# Wireless.net
KiCad netlist of a schematic drawn in Altium Designer
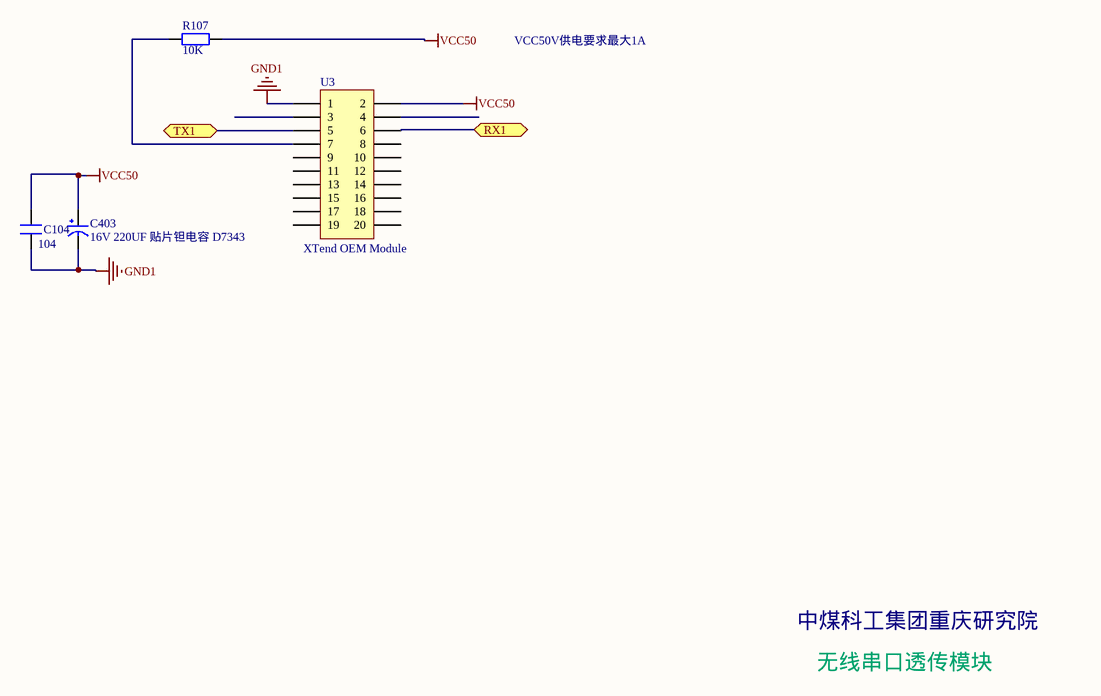
[diagram p0: Wireless.SchDoc]

(export (version "E")
  (design (tool "Eeschema 10.0.6"))
  (components
    (comp (ref "C104") (value "104") (footprint "1206") (libsource (lib "WarShip V3 STM32103封装库") (part "C")))
    (comp (ref "C403")
      (value "16V 220UF 贴片钽电容 D7343")
      (footprint "D型7343贴片钽电容")
      (libsource (lib "WarShip V3 STM32103封装库") (part "CAP"))
    )
    (comp (ref "R107")
      (value "10K")
      (footprint "1206")
      (description "Resistor")
      (fields (field (name "Comment") "Res2") (field (name "PUBLISHER") "Altium Limited"))
      (libsource (lib "Miscellaneous Devices") (part "Res2"))
    )
    (comp (ref "U3")
      (value "XTend OEM Module")
      (footprint "无线电台_PART_1")
      (description "Header, 10-Pin, Dual row")
      (fields (field (name "PUBLISHER") "Altium Limited"))
      (libsource (lib "Miscellaneous Connectors") (part "Header 10X2"))
    )
  )
  (nets
    (net (code "1") (name "/RX1") (class "Default")
      (node (ref "U3") (pin "6") (pinfunction "6_6") (pintype "passive"))
    )
    (net (code "2") (name "/TX1") (class "Default")
      (node (ref "U3") (pin "5") (pinfunction "5_5") (pintype "passive"))
    )
    (net (code "3") (name "GND1") (class "Default")
      (node (ref "C104") (pin "1") (pintype "passive"))
      (node (ref "C403") (pin "2") (pinfunction "GND_2") (pintype "passive"))
      (node (ref "U3") (pin "1") (pinfunction "1_1") (pintype "passive"))
    )
    (net (code "4") (name "Net-(R107-Pad1)") (class "Default")
      (node (ref "R107") (pin "1") (pinfunction "1_1") (pintype "passive"))
      (node (ref "U3") (pin "7") (pinfunction "7_7") (pintype "passive"))
    )
    (net (code "5") (name "VCC50") (class "Default")
      (node (ref "C104") (pin "2") (pintype "passive"))
      (node (ref "C403") (pin "1") (pinfunction "VCC_1") (pintype "passive"))
      (node (ref "R107") (pin "2") (pinfunction "2_2") (pintype "passive"))
      (node (ref "U3") (pin "2") (pinfunction "2_2") (pintype "passive"))
    )
    (net (code "6") (name "unconnected-(U3-Pad3)") (class "Default")
      (node (ref "U3") (pin "3") (pinfunction "3_3") (pintype "passive"))
    )
    (net (code "7") (name "unconnected-(U3-Pad4)") (class "Default")
      (node (ref "U3") (pin "4") (pinfunction "4_4") (pintype "passive"))
    )
    (net (code "8") (name "unconnected-(U3-Pad8)") (class "Default")
      (node (ref "U3") (pin "8") (pinfunction "8_8") (pintype "passive"))
    )
    (net (code "9") (name "unconnected-(U3-Pad9)") (class "Default")
      (node (ref "U3") (pin "9") (pinfunction "9_9") (pintype "passive"))
    )
    (net (code "10") (name "unconnected-(U3-Pad10)") (class "Default")
      (node (ref "U3") (pin "10") (pinfunction "10_10") (pintype "passive"))
    )
    (net (code "11") (name "unconnected-(U3-Pad11)") (class "Default")
      (node (ref "U3") (pin "11") (pinfunction "11_11") (pintype "passive"))
    )
    (net (code "12") (name "unconnected-(U3-Pad12)") (class "Default")
      (node (ref "U3") (pin "12") (pinfunction "12_12") (pintype "passive"))
    )
    (net (code "13") (name "unconnected-(U3-Pad13)") (class "Default")
      (node (ref "U3") (pin "13") (pinfunction "13_13") (pintype "passive"))
    )
    (net (code "14") (name "unconnected-(U3-Pad14)") (class "Default")
      (node (ref "U3") (pin "14") (pinfunction "14_14") (pintype "passive"))
    )
    (net (code "15") (name "unconnected-(U3-Pad15)") (class "Default")
      (node (ref "U3") (pin "15") (pinfunction "15_15") (pintype "passive"))
    )
    (net (code "16") (name "unconnected-(U3-Pad16)") (class "Default")
      (node (ref "U3") (pin "16") (pinfunction "16_16") (pintype "passive"))
    )
    (net (code "17") (name "unconnected-(U3-Pad17)") (class "Default")
      (node (ref "U3") (pin "17") (pinfunction "17_17") (pintype "passive"))
    )
    (net (code "18") (name "unconnected-(U3-Pad18)") (class "Default")
      (node (ref "U3") (pin "18") (pinfunction "18_18") (pintype "passive"))
    )
    (net (code "19") (name "unconnected-(U3-Pad19)") (class "Default")
      (node (ref "U3") (pin "19") (pinfunction "19_19") (pintype "passive"))
    )
    (net (code "20") (name "unconnected-(U3-Pad20)") (class "Default")
      (node (ref "U3") (pin "20") (pinfunction "20_20") (pintype "passive"))
    )
  )
)
